# corona-halo.net
KiCad netlist of a schematic drawn in EAGLE
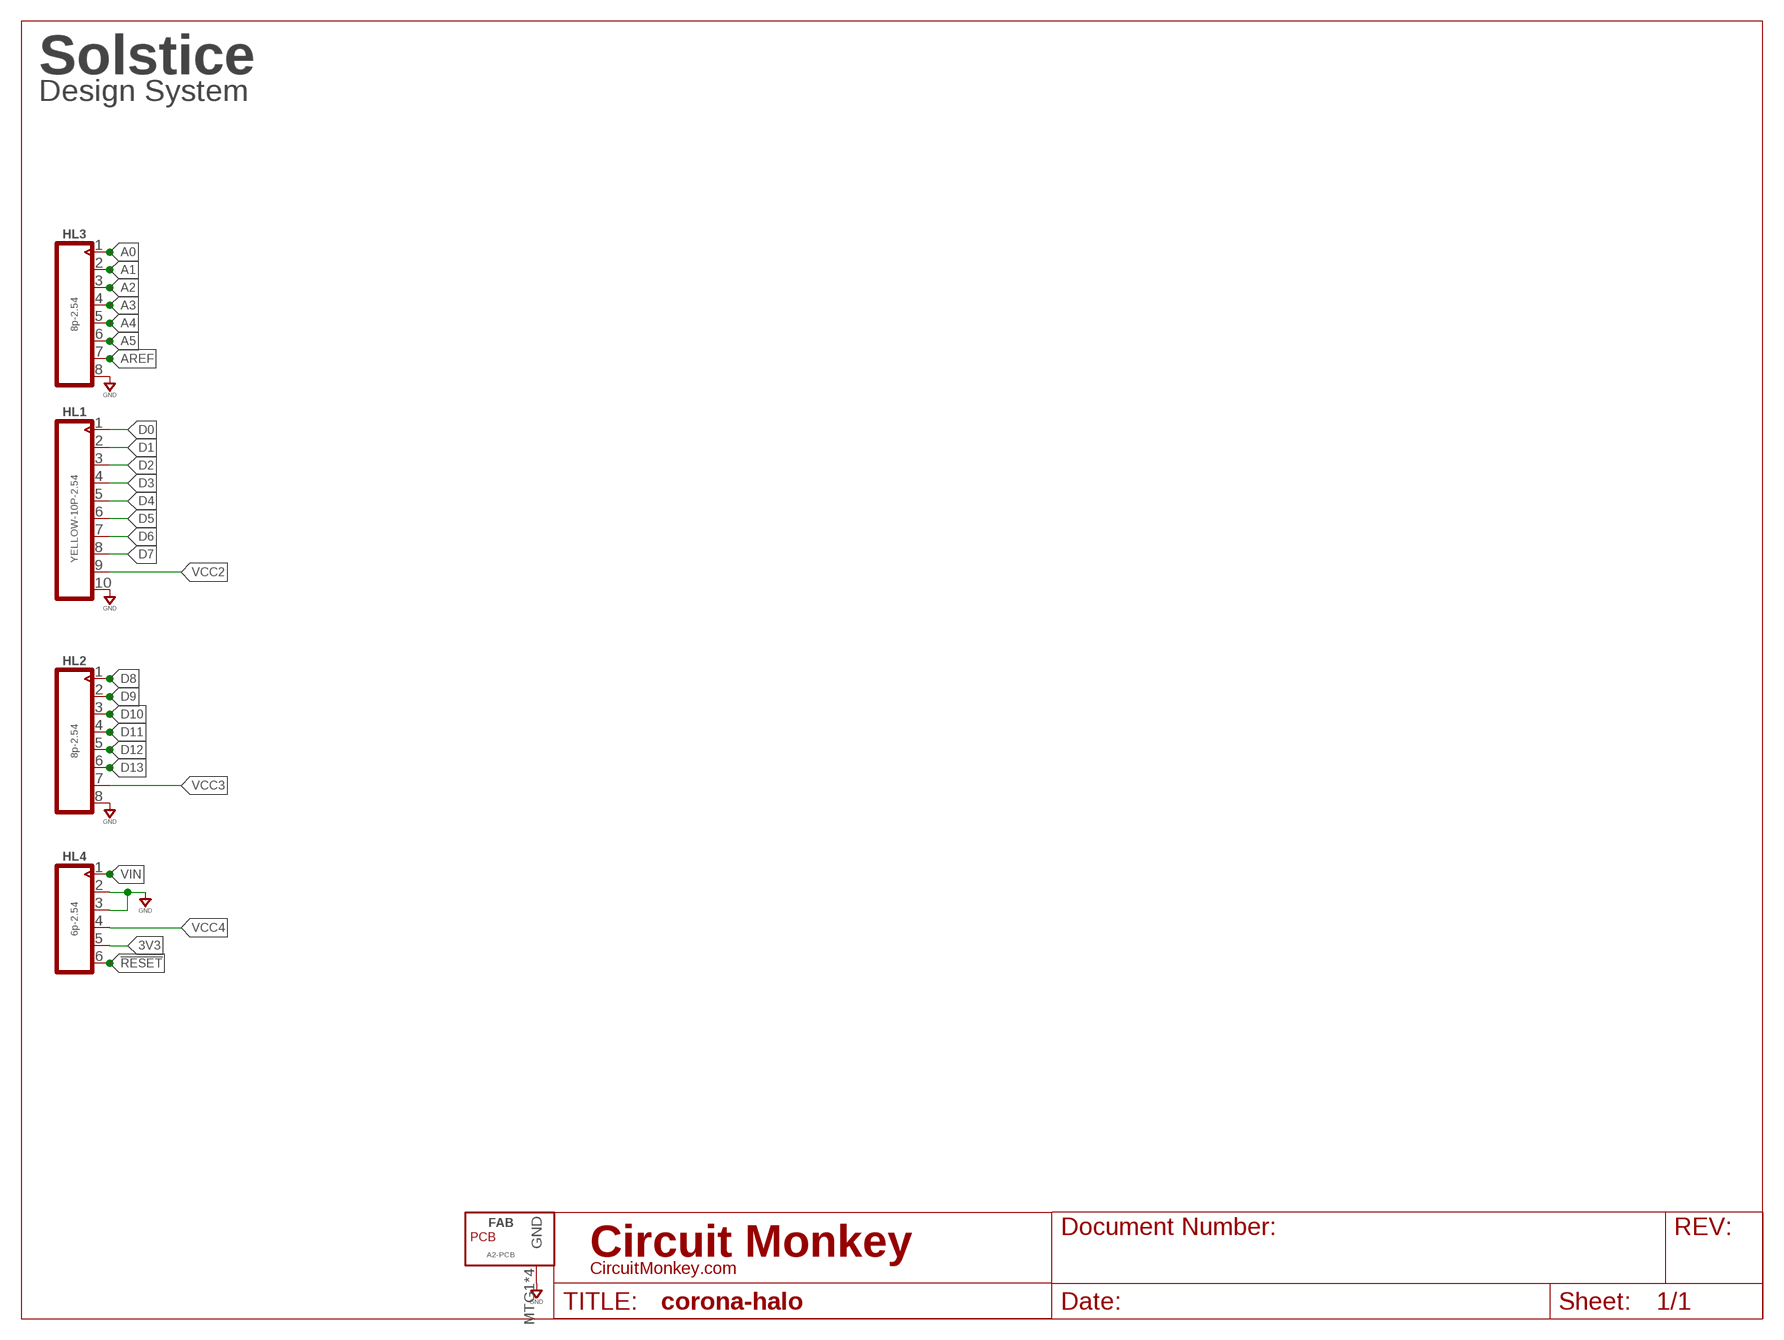
[diagram p0: schematic, sheet 1]

(export (version "E")
  (design (tool "Eeschema 10.0.6"))
  (components
    (comp (ref "FAB")
      (value "A2-PCB")
      (footprint "eagle-import:PCB-HALO-A2")
      (libsource (lib "eagle-import") (part "PCB-4-MTG-HALO-A2"))
    )
    (comp (ref "HL1")
      (value "YELLOW-10P-2.54")
      (footprint "eagle-import:H10-2.54")
      (fields (field (name "MPN") "F185-1110A1BSYC1"))
      (libsource (lib "eagle-import") (part "DIP-YELLOW-FEMALE-HEADER-VERT(10P-2.54)"))
    )
    (comp (ref "HL2")
      (value "8p-2.54")
      (footprint "eagle-import:H8-2.54")
      (fields (field (name "MPN") "F185-1108A1BSYC1"))
      (libsource (lib "eagle-import") (part "DIP-BLACK-FEMALE-HEADER-VERT(8P-2.54)"))
    )
    (comp (ref "HL3")
      (value "8p-2.54")
      (footprint "eagle-import:H8-2.54")
      (fields (field (name "MPN") "F185-1108A1BSYC1"))
      (libsource (lib "eagle-import") (part "DIP-BLACK-FEMALE-HEADER-VERT(8P-2.54)"))
    )
    (comp (ref "HL4")
      (value "6p-2.54")
      (footprint "eagle-import:H6-2.54")
      (fields (field (name "MPN") "F185-1106A1BSYC1"))
      (libsource (lib "eagle-import") (part "DIP-BLACK-FEMALE-HEADER-VERT(6P-2.54)"))
    )
  )
  (nets
    (net (code "1") (name "/~{RESET}") (class "Default")
      (node (ref "HL4") (pin "6") (pinfunction "6_6") (pintype "bidirectional"))
    )
    (net (code "2") (name "3V3") (class "Default")
      (node (ref "HL4") (pin "5") (pinfunction "5_5") (pintype "bidirectional"))
    )
    (net (code "3") (name "A0") (class "Default")
      (node (ref "HL3") (pin "1") (pinfunction "1_1") (pintype "bidirectional"))
    )
    (net (code "4") (name "A1") (class "Default")
      (node (ref "HL3") (pin "2") (pinfunction "2_2") (pintype "bidirectional"))
    )
    (net (code "5") (name "A2") (class "Default")
      (node (ref "HL3") (pin "3") (pinfunction "3_3") (pintype "bidirectional"))
    )
    (net (code "6") (name "A3") (class "Default")
      (node (ref "HL3") (pin "4") (pinfunction "4_4") (pintype "bidirectional"))
    )
    (net (code "7") (name "A4") (class "Default")
      (node (ref "HL3") (pin "5") (pinfunction "5_5") (pintype "bidirectional"))
    )
    (net (code "8") (name "A5") (class "Default")
      (node (ref "HL3") (pin "6") (pinfunction "6_6") (pintype "bidirectional"))
    )
    (net (code "9") (name "AREF") (class "Default")
      (node (ref "HL3") (pin "7") (pinfunction "7_7") (pintype "bidirectional"))
    )
    (net (code "10") (name "D0") (class "Default")
      (node (ref "HL1") (pin "1") (pinfunction "1_1") (pintype "bidirectional"))
    )
    (net (code "11") (name "D1") (class "Default")
      (node (ref "HL1") (pin "2") (pinfunction "2_2") (pintype "bidirectional"))
    )
    (net (code "12") (name "D2") (class "Default")
      (node (ref "HL1") (pin "3") (pinfunction "3_3") (pintype "bidirectional"))
    )
    (net (code "13") (name "D3") (class "Default")
      (node (ref "HL1") (pin "4") (pinfunction "4_4") (pintype "bidirectional"))
    )
    (net (code "14") (name "D4") (class "Default")
      (node (ref "HL1") (pin "5") (pinfunction "5_5") (pintype "bidirectional"))
    )
    (net (code "15") (name "D5") (class "Default")
      (node (ref "HL1") (pin "6") (pinfunction "6_6") (pintype "bidirectional"))
    )
    (net (code "16") (name "D6") (class "Default")
      (node (ref "HL1") (pin "7") (pinfunction "7_7") (pintype "bidirectional"))
    )
    (net (code "17") (name "D7") (class "Default")
      (node (ref "HL1") (pin "8") (pinfunction "8_8") (pintype "bidirectional"))
    )
    (net (code "18") (name "D8") (class "Default")
      (node (ref "HL2") (pin "1") (pinfunction "1_1") (pintype "bidirectional"))
    )
    (net (code "19") (name "D9") (class "Default")
      (node (ref "HL2") (pin "2") (pinfunction "2_2") (pintype "bidirectional"))
    )
    (net (code "20") (name "D10") (class "Default")
      (node (ref "HL2") (pin "3") (pinfunction "3_3") (pintype "bidirectional"))
    )
    (net (code "21") (name "D11") (class "Default")
      (node (ref "HL2") (pin "4") (pinfunction "4_4") (pintype "bidirectional"))
    )
    (net (code "22") (name "D12") (class "Default")
      (node (ref "HL2") (pin "5") (pinfunction "5_5") (pintype "bidirectional"))
    )
    (net (code "23") (name "D13") (class "Default")
      (node (ref "HL2") (pin "6") (pinfunction "6_6") (pintype "bidirectional"))
    )
    (net (code "24") (name "GND") (class "Default")
      (node (ref "FAB") (pin "MTG1") (pinfunction "GND_MTG1") (pintype "bidirectional"))
      (node (ref "FAB") (pin "MTG2") (pinfunction "GND_MTG2") (pintype "bidirectional"))
      (node (ref "FAB") (pin "MTG3") (pinfunction "GND_MTG3") (pintype "bidirectional"))
      (node (ref "FAB") (pin "MTG4") (pinfunction "GND_MTG4") (pintype "bidirectional"))
      (node (ref "HL1") (pin "10") (pinfunction "10_10") (pintype "bidirectional"))
      (node (ref "HL2") (pin "8") (pinfunction "8_8") (pintype "bidirectional"))
      (node (ref "HL3") (pin "8") (pinfunction "8_8") (pintype "bidirectional"))
      (node (ref "HL4") (pin "2") (pinfunction "2_2") (pintype "bidirectional"))
      (node (ref "HL4") (pin "3") (pinfunction "3_3") (pintype "bidirectional"))
    )
    (net (code "25") (name "VCC2") (class "Default")
      (node (ref "HL1") (pin "9") (pinfunction "9_9") (pintype "bidirectional"))
    )
    (net (code "26") (name "VCC3") (class "Default")
      (node (ref "HL2") (pin "7") (pinfunction "7_7") (pintype "bidirectional"))
    )
    (net (code "27") (name "VCC4") (class "Default")
      (node (ref "HL4") (pin "4") (pinfunction "4_4") (pintype "bidirectional"))
    )
    (net (code "28") (name "VIN") (class "Default")
      (node (ref "HL4") (pin "1") (pinfunction "1_1") (pintype "bidirectional"))
    )
  )
)
